# 5VAC-Dc.net
KiCad netlist of a schematic drawn in EAGLE
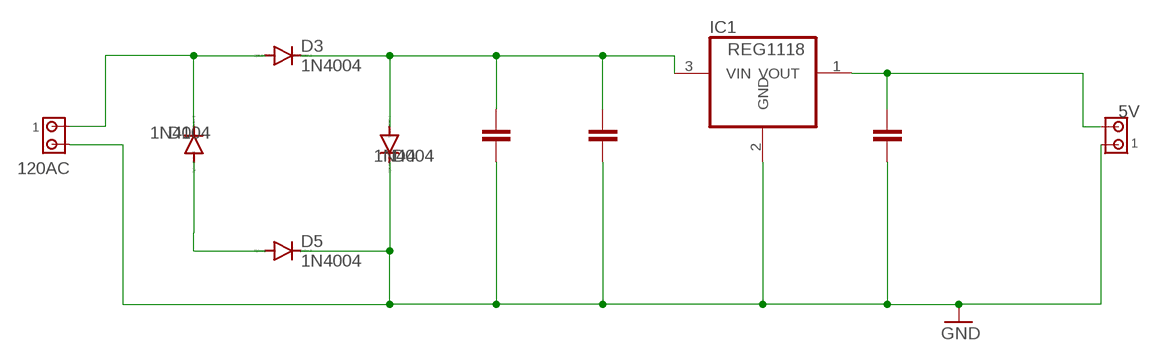
[diagram p0: schematic, sheet 1]

(export (version "E")
  (design (tool "Eeschema 10.0.6"))
  (components
    (comp (ref "5V")
      (value "1445055-2")
      (footprint "eagle-import:1445055-2")
      (libsource (lib "eagle-import") (part "1445055-2"))
    )
    (comp (ref "D1")
      (value "1N4004")
      (footprint "eagle-import:DO41-10")
      (libsource (lib "eagle-import") (part "1N4004"))
    )
    (comp (ref "D3")
      (value "1N4004")
      (footprint "eagle-import:DO41-10")
      (libsource (lib "eagle-import") (part "1N4004"))
    )
    (comp (ref "D4")
      (value "1N4004")
      (footprint "eagle-import:DO41-10")
      (libsource (lib "eagle-import") (part "1N4004"))
    )
    (comp (ref "D5")
      (value "1N4004")
      (footprint "eagle-import:DO41-10")
      (libsource (lib "eagle-import") (part "1N4004"))
    )
    (comp (ref "IC1")
      (value "REG1118")
      (footprint "eagle-import:SOT223")
      (fields (field (name "MPN") "REG1118-2.85/2K5G4"))
      (libsource (lib "eagle-import") (part "REG1118"))
    )
    (comp (ref "J1")
      (value "120AC")
      (footprint "eagle-import:1445055-2")
      (libsource (lib "eagle-import") (part "1445055-2"))
    )
  )
  (nets
    (net (code "1") (name "GND") (class "Default")
      (node (ref "5V") (pin "1") (pinfunction "1_1") (pintype "passive"))
      (node (ref "D4") (pin "C") (pinfunction "C_C") (pintype "passive"))
      (node (ref "D5") (pin "C") (pinfunction "C_C") (pintype "passive"))
      (node (ref "IC1") (pin "2") (pinfunction "GND_2") (pintype "power_in"))
      (node (ref "J1") (pin "2") (pinfunction "2_2") (pintype "passive"))
    )
    (net (code "2") (name "Net-(D1-PadA)") (class "Default")
      (node (ref "D1") (pin "A") (pinfunction "A_A") (pintype "passive"))
      (node (ref "D5") (pin "A") (pinfunction "A_A") (pintype "passive"))
    )
    (net (code "3") (name "Net-(D1-PadC)") (class "Default")
      (node (ref "D1") (pin "C") (pinfunction "C_C") (pintype "passive"))
      (node (ref "D3") (pin "A") (pinfunction "A_A") (pintype "passive"))
      (node (ref "J1") (pin "1") (pinfunction "1_1") (pintype "passive"))
    )
    (net (code "4") (name "Net-(IC1-VIN)") (class "Default")
      (node (ref "D3") (pin "C") (pinfunction "C_C") (pintype "passive"))
      (node (ref "D4") (pin "A") (pinfunction "A_A") (pintype "passive"))
      (node (ref "IC1") (pin "3") (pinfunction "VIN_3") (pintype "input"))
    )
    (net (code "5") (name "Net-(IC1-VOUT)") (class "Default")
      (node (ref "5V") (pin "2") (pinfunction "2_2") (pintype "passive"))
      (node (ref "IC1") (pin "1") (pinfunction "VOUT_1") (pintype "output"))
    )
  )
)
